# 411_Synth.net
KiCad netlist of a schematic drawn in EAGLE
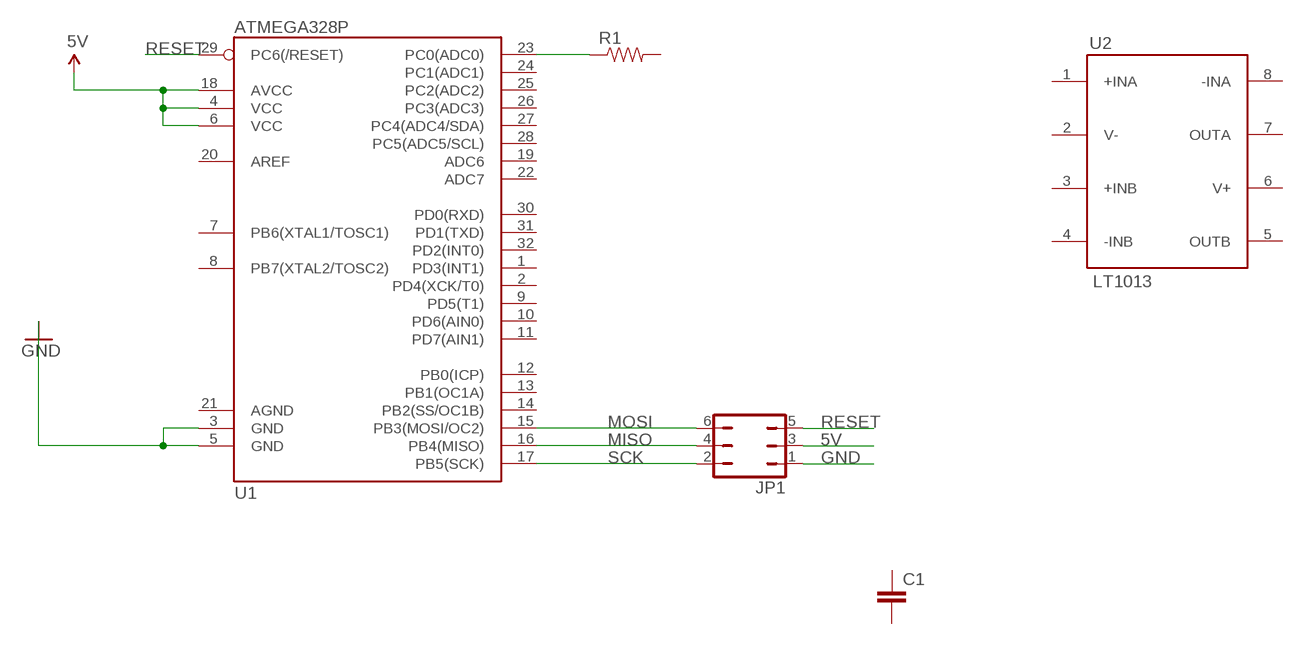
[diagram p0: schematic, sheet 1]

(export (version "E")
  (design (tool "Eeschema 10.0.6"))
  (components
    (comp (ref "C1")
      (value "CAP0603-CAP")
      (footprint "eagle-import:0603-CAP")
      (libsource (lib "eagle-import") (part "CAP0603-CAP"))
    )
    (comp (ref "JP1")
      (value "JP3Q")
      (footprint "eagle-import:JP3Q")
      (libsource (lib "eagle-import") (part "JP3Q"))
    )
    (comp (ref "R1")
      (value "RESISTOR0603")
      (footprint "eagle-import:0603-RES")
      (libsource (lib "eagle-import") (part "RESISTOR0603"))
    )
    (comp (ref "U1")
      (value "ATMEGA328P")
      (footprint "eagle-import:TQFP32-08")
      (libsource (lib "eagle-import") (part "ATMEGA328_SMT"))
    )
    (comp (ref "U2")
      (value "LT1013")
      (footprint "eagle-import:SO08")
      (libsource (lib "eagle-import") (part "LT1013"))
    )
  )
  (nets
    (net (code "1") (name "/MISO") (class "Default")
      (node (ref "JP1") (pin "4") (pinfunction "4_4") (pintype "passive"))
      (node (ref "U1") (pin "16") (pinfunction "PB4(MISO)_16") (pintype "bidirectional"))
    )
    (net (code "2") (name "/MOSI") (class "Default")
      (node (ref "JP1") (pin "6") (pinfunction "6_6") (pintype "passive"))
      (node (ref "U1") (pin "15") (pinfunction "PB3(MOSI/OC2)_15") (pintype "bidirectional"))
    )
    (net (code "3") (name "/RESET") (class "Default")
      (node (ref "JP1") (pin "5") (pinfunction "5_5") (pintype "passive"))
      (node (ref "U1") (pin "29") (pinfunction "PC6(/RESET)_29") (pintype "bidirectional"))
    )
    (net (code "4") (name "/SCK") (class "Default")
      (node (ref "JP1") (pin "2") (pinfunction "2_2") (pintype "passive"))
      (node (ref "U1") (pin "17") (pinfunction "PB5(SCK)_17") (pintype "bidirectional"))
    )
    (net (code "5") (name "/V+") (class "Default")
      (node (ref "U2") (pin "6") (pinfunction "V+_6") (pintype "power_in"))
    )
    (net (code "6") (name "/V-") (class "Default")
      (node (ref "U2") (pin "2") (pinfunction "V-_2") (pintype "power_in"))
    )
    (net (code "7") (name "5V") (class "Default")
      (node (ref "JP1") (pin "3") (pinfunction "3_3") (pintype "passive"))
      (node (ref "U1") (pin "18") (pinfunction "AVCC_18") (pintype "bidirectional"))
      (node (ref "U1") (pin "4") (pinfunction "VCC_4") (pintype "bidirectional"))
      (node (ref "U1") (pin "6") (pinfunction "VCC_6") (pintype "bidirectional"))
    )
    (net (code "8") (name "GND") (class "Default")
      (node (ref "JP1") (pin "1") (pinfunction "1_1") (pintype "passive"))
      (node (ref "U1") (pin "3") (pinfunction "GND_3") (pintype "bidirectional"))
      (node (ref "U1") (pin "5") (pinfunction "GND_5") (pintype "bidirectional"))
    )
    (net (code "9") (name "Net-(U1-PC0(ADC0))") (class "Default")
      (node (ref "R1") (pin "1") (pinfunction "1_1") (pintype "passive"))
      (node (ref "U1") (pin "23") (pinfunction "PC0(ADC0)_23") (pintype "bidirectional"))
    )
    (net (code "10") (name "unconnected-(C1-Pad1)") (class "Default")
      (node (ref "C1") (pin "1") (pinfunction "1_1") (pintype "passive"))
    )
    (net (code "11") (name "unconnected-(C1-Pad2)") (class "Default")
      (node (ref "C1") (pin "2") (pinfunction "2_2") (pintype "passive"))
    )
    (net (code "12") (name "unconnected-(R1-Pad2)") (class "Default")
      (node (ref "R1") (pin "2") (pinfunction "2_2") (pintype "passive"))
    )
    (net (code "13") (name "unconnected-(U1-ADC6-Pad19)") (class "Default")
      (node (ref "U1") (pin "19") (pinfunction "ADC6_19") (pintype "bidirectional"))
    )
    (net (code "14") (name "unconnected-(U1-ADC7-Pad22)") (class "Default")
      (node (ref "U1") (pin "22") (pinfunction "ADC7_22") (pintype "bidirectional"))
    )
    (net (code "15") (name "unconnected-(U1-AGND-Pad21)") (class "Default")
      (node (ref "U1") (pin "21") (pinfunction "AGND_21") (pintype "bidirectional"))
    )
    (net (code "16") (name "unconnected-(U1-AREF-Pad20)") (class "Default")
      (node (ref "U1") (pin "20") (pinfunction "AREF_20") (pintype "bidirectional"))
    )
    (net (code "17") (name "unconnected-(U1-PB0(ICP)-Pad12)") (class "Default")
      (node (ref "U1") (pin "12") (pinfunction "PB0(ICP)_12") (pintype "bidirectional"))
    )
    (net (code "18") (name "unconnected-(U1-PB1(OC1A)-Pad13)") (class "Default")
      (node (ref "U1") (pin "13") (pinfunction "PB1(OC1A)_13") (pintype "bidirectional"))
    )
    (net (code "19") (name "unconnected-(U1-PB2(SS{slash}OC1B)-Pad14)") (class "Default")
      (node (ref "U1") (pin "14") (pinfunction "PB2(SS/OC1B)_14") (pintype "bidirectional"))
    )
    (net (code "20") (name "unconnected-(U1-PB6(XTAL1{slash}TOSC1)-Pad7)") (class "Default")
      (node (ref "U1") (pin "7") (pinfunction "PB6(XTAL1/TOSC1)_7") (pintype "bidirectional"))
    )
    (net (code "21") (name "unconnected-(U1-PB7(XTAL2{slash}TOSC2)-Pad8)") (class "Default")
      (node (ref "U1") (pin "8") (pinfunction "PB7(XTAL2/TOSC2)_8") (pintype "bidirectional"))
    )
    (net (code "22") (name "unconnected-(U1-PC1(ADC1)-Pad24)") (class "Default")
      (node (ref "U1") (pin "24") (pinfunction "PC1(ADC1)_24") (pintype "bidirectional"))
    )
    (net (code "23") (name "unconnected-(U1-PC2(ADC2)-Pad25)") (class "Default")
      (node (ref "U1") (pin "25") (pinfunction "PC2(ADC2)_25") (pintype "bidirectional"))
    )
    (net (code "24") (name "unconnected-(U1-PC3(ADC3)-Pad26)") (class "Default")
      (node (ref "U1") (pin "26") (pinfunction "PC3(ADC3)_26") (pintype "bidirectional"))
    )
    (net (code "25") (name "unconnected-(U1-PC4(ADC4{slash}SDA)-Pad27)") (class "Default")
      (node (ref "U1") (pin "27") (pinfunction "PC4(ADC4/SDA)_27") (pintype "bidirectional"))
    )
    (net (code "26") (name "unconnected-(U1-PC5(ADC5{slash}SCL)-Pad28)") (class "Default")
      (node (ref "U1") (pin "28") (pinfunction "PC5(ADC5/SCL)_28") (pintype "bidirectional"))
    )
    (net (code "27") (name "unconnected-(U1-PD0(RXD)-Pad30)") (class "Default")
      (node (ref "U1") (pin "30") (pinfunction "PD0(RXD)_30") (pintype "bidirectional"))
    )
    (net (code "28") (name "unconnected-(U1-PD1(TXD)-Pad31)") (class "Default")
      (node (ref "U1") (pin "31") (pinfunction "PD1(TXD)_31") (pintype "bidirectional"))
    )
    (net (code "29") (name "unconnected-(U1-PD2(INT0)-Pad32)") (class "Default")
      (node (ref "U1") (pin "32") (pinfunction "PD2(INT0)_32") (pintype "bidirectional"))
    )
    (net (code "30") (name "unconnected-(U1-PD3(INT1)-Pad1)") (class "Default")
      (node (ref "U1") (pin "1") (pinfunction "PD3(INT1)_1") (pintype "bidirectional"))
    )
    (net (code "31") (name "unconnected-(U1-PD4(XCK{slash}T0)-Pad2)") (class "Default")
      (node (ref "U1") (pin "2") (pinfunction "PD4(XCK/T0)_2") (pintype "bidirectional"))
    )
    (net (code "32") (name "unconnected-(U1-PD5(T1)-Pad9)") (class "Default")
      (node (ref "U1") (pin "9") (pinfunction "PD5(T1)_9") (pintype "bidirectional"))
    )
    (net (code "33") (name "unconnected-(U1-PD6(AIN0)-Pad10)") (class "Default")
      (node (ref "U1") (pin "10") (pinfunction "PD6(AIN0)_10") (pintype "bidirectional"))
    )
    (net (code "34") (name "unconnected-(U1-PD7(AIN1)-Pad11)") (class "Default")
      (node (ref "U1") (pin "11") (pinfunction "PD7(AIN1)_11") (pintype "bidirectional"))
    )
    (net (code "35") (name "unconnected-(U2-+INA-Pad1)") (class "Default")
      (node (ref "U2") (pin "1") (pinfunction "+INA_1") (pintype "bidirectional"))
    )
    (net (code "36") (name "unconnected-(U2-+INB-Pad3)") (class "Default")
      (node (ref "U2") (pin "3") (pinfunction "+INB_3") (pintype "bidirectional"))
    )
    (net (code "37") (name "unconnected-(U2--INA-Pad8)") (class "Default")
      (node (ref "U2") (pin "8") (pinfunction "-INA_8") (pintype "bidirectional"))
    )
    (net (code "38") (name "unconnected-(U2--INB-Pad4)") (class "Default")
      (node (ref "U2") (pin "4") (pinfunction "-INB_4") (pintype "bidirectional"))
    )
    (net (code "39") (name "unconnected-(U2-OUTA-Pad7)") (class "Default")
      (node (ref "U2") (pin "7") (pinfunction "OUTA_7") (pintype "bidirectional"))
    )
    (net (code "40") (name "unconnected-(U2-OUTB-Pad5)") (class "Default")
      (node (ref "U2") (pin "5") (pinfunction "OUTB_5") (pintype "bidirectional"))
    )
  )
)
